# LED_Array.net
KiCad netlist of a schematic drawn in Altium Designer
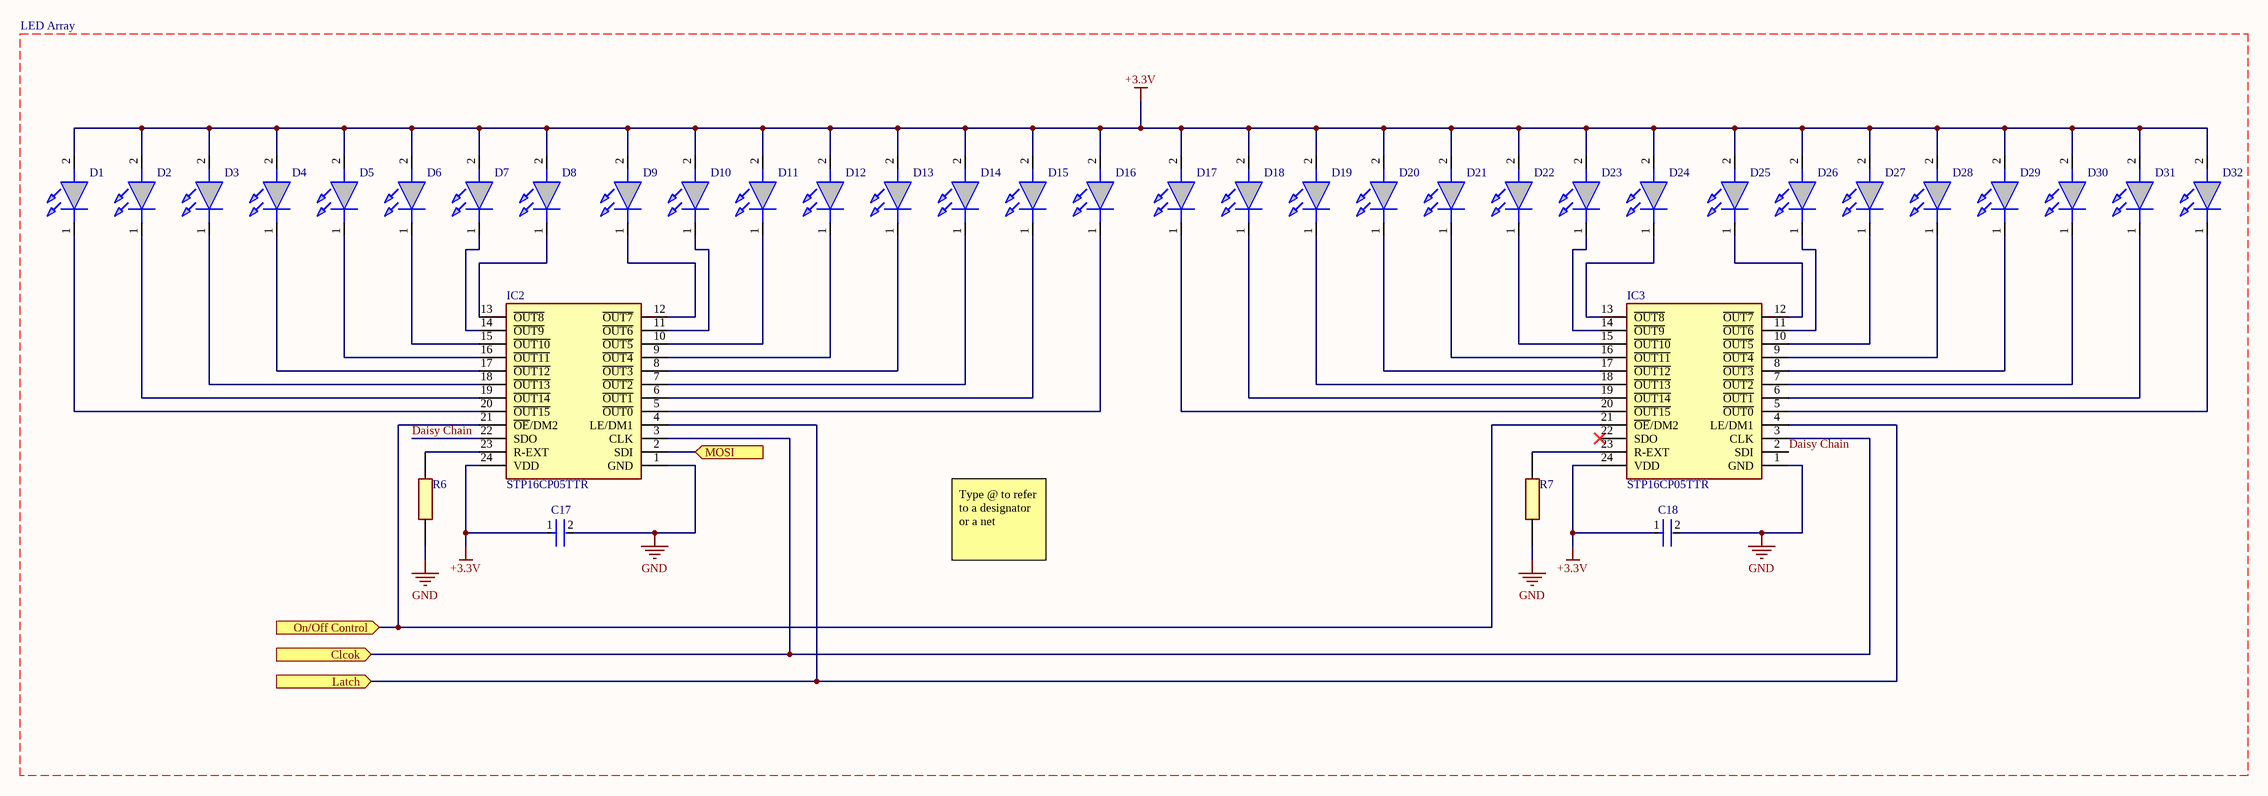
[diagram p0: LED_Array.SchDoc]

(export (version "E")
  (design (tool "Eeschema 10.0.6"))
  (components
    (comp (ref "C17")
      (value "CL31B104KBP5PNF")
      (footprint "FP-CL31-IPC_C")
      (description "Cap Ceramic 100nF 50V X7R ±10% SMD 1206 +125°C Embossed T/R")
      (fields (field (name "TOLERANCE") "10%"))
      (libsource (lib "Altium Content Vault") (part "b4654b650e69147ec39a6b967a45e02"))
    )
    (comp (ref "C18")
      (value "CL31B104KBP5PNF")
      (footprint "FP-CL31-IPC_C")
      (description "Cap Ceramic 100nF 50V X7R ±10% SMD 1206 +125°C Embossed T/R")
      (fields (field (name "TOLERANCE") "10%"))
      (libsource (lib "Altium Content Vault") (part "b4654b650e69147ec39a6b967a45e02"))
    )
    (comp (ref "D1")
      (value "LR_T64F-BBDB-1-1")
      (footprint "LEDM3528X380N")
      (description "Standard LEDs - SMD Red")
      (fields
        (field (name "MOUSER PART NUMBER") "720-LRT64FBBDB11")
        (field (name "MANUFACTURER_PART_NUMBER") "LR T64F-BBDB-1-1")
      )
      (libsource (lib "LR_T64F-BBDB-1-1") (part "LR_T64F-BBDB-1-1"))
    )
    (comp (ref "D2")
      (value "LR_T64F-BBDB-1-1")
      (footprint "LEDM3528X380N")
      (description "Standard LEDs - SMD Red")
      (fields
        (field (name "MOUSER PART NUMBER") "720-LRT64FBBDB11")
        (field (name "MANUFACTURER_PART_NUMBER") "LR T64F-BBDB-1-1")
      )
      (libsource (lib "LR_T64F-BBDB-1-1") (part "LR_T64F-BBDB-1-1"))
    )
    (comp (ref "D3")
      (value "LR_T64F-BBDB-1-1")
      (footprint "LEDM3528X380N")
      (description "Standard LEDs - SMD Red")
      (fields
        (field (name "MOUSER PART NUMBER") "720-LRT64FBBDB11")
        (field (name "MANUFACTURER_PART_NUMBER") "LR T64F-BBDB-1-1")
      )
      (libsource (lib "LR_T64F-BBDB-1-1") (part "LR_T64F-BBDB-1-1"))
    )
    (comp (ref "D4")
      (value "LR_T64F-BBDB-1-1")
      (footprint "LEDM3528X380N")
      (description "Standard LEDs - SMD Red")
      (fields
        (field (name "MOUSER PART NUMBER") "720-LRT64FBBDB11")
        (field (name "MANUFACTURER_PART_NUMBER") "LR T64F-BBDB-1-1")
      )
      (libsource (lib "LR_T64F-BBDB-1-1") (part "LR_T64F-BBDB-1-1"))
    )
    (comp (ref "D5")
      (value "LR_T64F-BBDB-1-1")
      (footprint "LEDM3528X380N")
      (description "Standard LEDs - SMD Red")
      (fields
        (field (name "MOUSER PART NUMBER") "720-LRT64FBBDB11")
        (field (name "MANUFACTURER_PART_NUMBER") "LR T64F-BBDB-1-1")
      )
      (libsource (lib "LR_T64F-BBDB-1-1") (part "LR_T64F-BBDB-1-1"))
    )
    (comp (ref "D6")
      (value "LR_T64F-BBDB-1-1")
      (footprint "LEDM3528X380N")
      (description "Standard LEDs - SMD Red")
      (fields
        (field (name "MOUSER PART NUMBER") "720-LRT64FBBDB11")
        (field (name "MANUFACTURER_PART_NUMBER") "LR T64F-BBDB-1-1")
      )
      (libsource (lib "LR_T64F-BBDB-1-1") (part "LR_T64F-BBDB-1-1"))
    )
    (comp (ref "D7")
      (value "LR_T64F-BBDB-1-1")
      (footprint "LEDM3528X380N")
      (description "Standard LEDs - SMD Red")
      (fields
        (field (name "MOUSER PART NUMBER") "720-LRT64FBBDB11")
        (field (name "MANUFACTURER_PART_NUMBER") "LR T64F-BBDB-1-1")
      )
      (libsource (lib "LR_T64F-BBDB-1-1") (part "LR_T64F-BBDB-1-1"))
    )
    (comp (ref "D8")
      (value "LR_T64F-BBDB-1-1")
      (footprint "LEDM3528X380N")
      (description "Standard LEDs - SMD Red")
      (fields
        (field (name "MOUSER PART NUMBER") "720-LRT64FBBDB11")
        (field (name "MANUFACTURER_PART_NUMBER") "LR T64F-BBDB-1-1")
      )
      (libsource (lib "LR_T64F-BBDB-1-1") (part "LR_T64F-BBDB-1-1"))
    )
    (comp (ref "D9")
      (value "LR_T64F-BBDB-1-1")
      (footprint "LEDM3528X380N")
      (description "Standard LEDs - SMD Red")
      (fields
        (field (name "MOUSER PART NUMBER") "720-LRT64FBBDB11")
        (field (name "MANUFACTURER_PART_NUMBER") "LR T64F-BBDB-1-1")
      )
      (libsource (lib "LR_T64F-BBDB-1-1") (part "LR_T64F-BBDB-1-1"))
    )
    (comp (ref "D10")
      (value "LR_T64F-BBDB-1-1")
      (footprint "LEDM3528X380N")
      (description "Standard LEDs - SMD Red")
      (fields
        (field (name "MOUSER PART NUMBER") "720-LRT64FBBDB11")
        (field (name "MANUFACTURER_PART_NUMBER") "LR T64F-BBDB-1-1")
      )
      (libsource (lib "LR_T64F-BBDB-1-1") (part "LR_T64F-BBDB-1-1"))
    )
    (comp (ref "D11")
      (value "LR_T64F-BBDB-1-1")
      (footprint "LEDM3528X380N")
      (description "Standard LEDs - SMD Red")
      (fields
        (field (name "MOUSER PART NUMBER") "720-LRT64FBBDB11")
        (field (name "MANUFACTURER_PART_NUMBER") "LR T64F-BBDB-1-1")
      )
      (libsource (lib "LR_T64F-BBDB-1-1") (part "LR_T64F-BBDB-1-1"))
    )
    (comp (ref "D12")
      (value "LR_T64F-BBDB-1-1")
      (footprint "LEDM3528X380N")
      (description "Standard LEDs - SMD Red")
      (fields
        (field (name "MOUSER PART NUMBER") "720-LRT64FBBDB11")
        (field (name "MANUFACTURER_PART_NUMBER") "LR T64F-BBDB-1-1")
      )
      (libsource (lib "LR_T64F-BBDB-1-1") (part "LR_T64F-BBDB-1-1"))
    )
    (comp (ref "D13")
      (value "LR_T64F-BBDB-1-1")
      (footprint "LEDM3528X380N")
      (description "Standard LEDs - SMD Red")
      (fields
        (field (name "MOUSER PART NUMBER") "720-LRT64FBBDB11")
        (field (name "MANUFACTURER_PART_NUMBER") "LR T64F-BBDB-1-1")
      )
      (libsource (lib "LR_T64F-BBDB-1-1") (part "LR_T64F-BBDB-1-1"))
    )
    (comp (ref "D14")
      (value "LR_T64F-BBDB-1-1")
      (footprint "LEDM3528X380N")
      (description "Standard LEDs - SMD Red")
      (fields
        (field (name "MOUSER PART NUMBER") "720-LRT64FBBDB11")
        (field (name "MANUFACTURER_PART_NUMBER") "LR T64F-BBDB-1-1")
      )
      (libsource (lib "LR_T64F-BBDB-1-1") (part "LR_T64F-BBDB-1-1"))
    )
    (comp (ref "D15")
      (value "LR_T64F-BBDB-1-1")
      (footprint "LEDM3528X380N")
      (description "Standard LEDs - SMD Red")
      (fields
        (field (name "MOUSER PART NUMBER") "720-LRT64FBBDB11")
        (field (name "MANUFACTURER_PART_NUMBER") "LR T64F-BBDB-1-1")
      )
      (libsource (lib "LR_T64F-BBDB-1-1") (part "LR_T64F-BBDB-1-1"))
    )
    (comp (ref "D16")
      (value "LR_T64F-BBDB-1-1")
      (footprint "LEDM3528X380N")
      (description "Standard LEDs - SMD Red")
      (fields
        (field (name "MOUSER PART NUMBER") "720-LRT64FBBDB11")
        (field (name "MANUFACTURER_PART_NUMBER") "LR T64F-BBDB-1-1")
      )
      (libsource (lib "LR_T64F-BBDB-1-1") (part "LR_T64F-BBDB-1-1"))
    )
    (comp (ref "D17")
      (value "LR_T64F-BBDB-1-1")
      (footprint "LEDM3528X380N")
      (description "Standard LEDs - SMD Red")
      (fields
        (field (name "MOUSER PART NUMBER") "720-LRT64FBBDB11")
        (field (name "MANUFACTURER_PART_NUMBER") "LR T64F-BBDB-1-1")
      )
      (libsource (lib "LR_T64F-BBDB-1-1") (part "LR_T64F-BBDB-1-1"))
    )
    (comp (ref "D18")
      (value "LR_T64F-BBDB-1-1")
      (footprint "LEDM3528X380N")
      (description "Standard LEDs - SMD Red")
      (fields
        (field (name "MOUSER PART NUMBER") "720-LRT64FBBDB11")
        (field (name "MANUFACTURER_PART_NUMBER") "LR T64F-BBDB-1-1")
      )
      (libsource (lib "LR_T64F-BBDB-1-1") (part "LR_T64F-BBDB-1-1"))
    )
    (comp (ref "D19")
      (value "LR_T64F-BBDB-1-1")
      (footprint "LEDM3528X380N")
      (description "Standard LEDs - SMD Red")
      (fields
        (field (name "MOUSER PART NUMBER") "720-LRT64FBBDB11")
        (field (name "MANUFACTURER_PART_NUMBER") "LR T64F-BBDB-1-1")
      )
      (libsource (lib "LR_T64F-BBDB-1-1") (part "LR_T64F-BBDB-1-1"))
    )
    (comp (ref "D20")
      (value "LR_T64F-BBDB-1-1")
      (footprint "LEDM3528X380N")
      (description "Standard LEDs - SMD Red")
      (fields
        (field (name "MOUSER PART NUMBER") "720-LRT64FBBDB11")
        (field (name "MANUFACTURER_PART_NUMBER") "LR T64F-BBDB-1-1")
      )
      (libsource (lib "LR_T64F-BBDB-1-1") (part "LR_T64F-BBDB-1-1"))
    )
    (comp (ref "D21")
      (value "LR_T64F-BBDB-1-1")
      (footprint "LEDM3528X380N")
      (description "Standard LEDs - SMD Red")
      (fields
        (field (name "MOUSER PART NUMBER") "720-LRT64FBBDB11")
        (field (name "MANUFACTURER_PART_NUMBER") "LR T64F-BBDB-1-1")
      )
      (libsource (lib "LR_T64F-BBDB-1-1") (part "LR_T64F-BBDB-1-1"))
    )
    (comp (ref "D22")
      (value "LR_T64F-BBDB-1-1")
      (footprint "LEDM3528X380N")
      (description "Standard LEDs - SMD Red")
      (fields
        (field (name "MOUSER PART NUMBER") "720-LRT64FBBDB11")
        (field (name "MANUFACTURER_PART_NUMBER") "LR T64F-BBDB-1-1")
      )
      (libsource (lib "LR_T64F-BBDB-1-1") (part "LR_T64F-BBDB-1-1"))
    )
    (comp (ref "D23")
      (value "LR_T64F-BBDB-1-1")
      (footprint "LEDM3528X380N")
      (description "Standard LEDs - SMD Red")
      (fields
        (field (name "MOUSER PART NUMBER") "720-LRT64FBBDB11")
        (field (name "MANUFACTURER_PART_NUMBER") "LR T64F-BBDB-1-1")
      )
      (libsource (lib "LR_T64F-BBDB-1-1") (part "LR_T64F-BBDB-1-1"))
    )
    (comp (ref "D24")
      (value "LR_T64F-BBDB-1-1")
      (footprint "LEDM3528X380N")
      (description "Standard LEDs - SMD Red")
      (fields
        (field (name "MOUSER PART NUMBER") "720-LRT64FBBDB11")
        (field (name "MANUFACTURER_PART_NUMBER") "LR T64F-BBDB-1-1")
      )
      (libsource (lib "LR_T64F-BBDB-1-1") (part "LR_T64F-BBDB-1-1"))
    )
    (comp (ref "D25")
      (value "LR_T64F-BBDB-1-1")
      (footprint "LEDM3528X380N")
      (description "Standard LEDs - SMD Red")
      (fields
        (field (name "MOUSER PART NUMBER") "720-LRT64FBBDB11")
        (field (name "MANUFACTURER_PART_NUMBER") "LR T64F-BBDB-1-1")
      )
      (libsource (lib "LR_T64F-BBDB-1-1") (part "LR_T64F-BBDB-1-1"))
    )
    (comp (ref "D26")
      (value "LR_T64F-BBDB-1-1")
      (footprint "LEDM3528X380N")
      (description "Standard LEDs - SMD Red")
      (fields
        (field (name "MOUSER PART NUMBER") "720-LRT64FBBDB11")
        (field (name "MANUFACTURER_PART_NUMBER") "LR T64F-BBDB-1-1")
      )
      (libsource (lib "LR_T64F-BBDB-1-1") (part "LR_T64F-BBDB-1-1"))
    )
    (comp (ref "D27")
      (value "LR_T64F-BBDB-1-1")
      (footprint "LEDM3528X380N")
      (description "Standard LEDs - SMD Red")
      (fields
        (field (name "MOUSER PART NUMBER") "720-LRT64FBBDB11")
        (field (name "MANUFACTURER_PART_NUMBER") "LR T64F-BBDB-1-1")
      )
      (libsource (lib "LR_T64F-BBDB-1-1") (part "LR_T64F-BBDB-1-1"))
    )
    (comp (ref "D28")
      (value "LR_T64F-BBDB-1-1")
      (footprint "LEDM3528X380N")
      (description "Standard LEDs - SMD Red")
      (fields
        (field (name "MOUSER PART NUMBER") "720-LRT64FBBDB11")
        (field (name "MANUFACTURER_PART_NUMBER") "LR T64F-BBDB-1-1")
      )
      (libsource (lib "LR_T64F-BBDB-1-1") (part "LR_T64F-BBDB-1-1"))
    )
    (comp (ref "D29")
      (value "LR_T64F-BBDB-1-1")
      (footprint "LEDM3528X380N")
      (description "Standard LEDs - SMD Red")
      (fields
        (field (name "MOUSER PART NUMBER") "720-LRT64FBBDB11")
        (field (name "MANUFACTURER_PART_NUMBER") "LR T64F-BBDB-1-1")
      )
      (libsource (lib "LR_T64F-BBDB-1-1") (part "LR_T64F-BBDB-1-1"))
    )
    (comp (ref "D30")
      (value "LR_T64F-BBDB-1-1")
      (footprint "LEDM3528X380N")
      (description "Standard LEDs - SMD Red")
      (fields
        (field (name "MOUSER PART NUMBER") "720-LRT64FBBDB11")
        (field (name "MANUFACTURER_PART_NUMBER") "LR T64F-BBDB-1-1")
      )
      (libsource (lib "LR_T64F-BBDB-1-1") (part "LR_T64F-BBDB-1-1"))
    )
    (comp (ref "D31")
      (value "LR_T64F-BBDB-1-1")
      (footprint "LEDM3528X380N")
      (description "Standard LEDs - SMD Red")
      (fields
        (field (name "MOUSER PART NUMBER") "720-LRT64FBBDB11")
        (field (name "MANUFACTURER_PART_NUMBER") "LR T64F-BBDB-1-1")
      )
      (libsource (lib "LR_T64F-BBDB-1-1") (part "LR_T64F-BBDB-1-1"))
    )
    (comp (ref "D32")
      (value "LR_T64F-BBDB-1-1")
      (footprint "LEDM3528X380N")
      (description "Standard LEDs - SMD Red")
      (fields
        (field (name "MOUSER PART NUMBER") "720-LRT64FBBDB11")
        (field (name "MANUFACTURER_PART_NUMBER") "LR T64F-BBDB-1-1")
      )
      (libsource (lib "LR_T64F-BBDB-1-1") (part "LR_T64F-BBDB-1-1"))
    )
    (comp (ref "IC2")
      (value "STP16CP05TTR")
      (footprint "SOP65P638X110-24N")
      (description "STMICROELECTRONICS - STP16CP05TTR - IC LED SINK DRIVER, 16-BIT, LO V")
      (fields (field (name "MOUSER PART NUMBER") "511-STP16CP05TTR"))
      (libsource (lib "STP16CP05TTR") (part "STP16CP05TTR"))
    )
    (comp (ref "IC3")
      (value "STP16CP05TTR")
      (footprint "SOP65P638X110-24N")
      (description "STMICROELECTRONICS - STP16CP05TTR - IC LED SINK DRIVER, 16-BIT, LO V")
      (fields (field (name "MOUSER PART NUMBER") "511-STP16CP05TTR"))
      (libsource (lib "STP16CP05TTR") (part "STP16CP05TTR"))
    )
    (comp (ref "R6")
      (value "ERA-8APB122V")
      (footprint "RESC3216X70N")
      (description "Thin Film Resistors - SMD 1206 Thin film chip resistor")
      (fields (field (name "MOUSER PART NUMBER") "667-ERA-8APB122V"))
      (libsource (lib "ERA-8APB122V") (part "ERA-8APB122V"))
    )
    (comp (ref "R7")
      (value "ERA-8APB122V")
      (footprint "RESC3216X70N")
      (description "Thin Film Resistors - SMD 1206 Thin film chip resistor")
      (fields (field (name "MOUSER PART NUMBER") "667-ERA-8APB122V"))
      (libsource (lib "ERA-8APB122V") (part "ERA-8APB122V"))
    )
  )
  (nets
    (net (code "1") (name "+3.3V") (class "Default")
      (node (ref "C17") (pin "1") (pinfunction "1_1") (pintype "passive"))
      (node (ref "C18") (pin "1") (pinfunction "1_1") (pintype "passive"))
      (node (ref "D1") (pin "2") (pinfunction "A_2") (pintype "passive"))
      (node (ref "D10") (pin "2") (pinfunction "A_2") (pintype "passive"))
      (node (ref "D11") (pin "2") (pinfunction "A_2") (pintype "passive"))
      (node (ref "D12") (pin "2") (pinfunction "A_2") (pintype "passive"))
      (node (ref "D13") (pin "2") (pinfunction "A_2") (pintype "passive"))
      (node (ref "D14") (pin "2") (pinfunction "A_2") (pintype "passive"))
      (node (ref "D15") (pin "2") (pinfunction "A_2") (pintype "passive"))
      (node (ref "D16") (pin "2") (pinfunction "A_2") (pintype "passive"))
      (node (ref "D17") (pin "2") (pinfunction "A_2") (pintype "passive"))
      (node (ref "D18") (pin "2") (pinfunction "A_2") (pintype "passive"))
      (node (ref "D19") (pin "2") (pinfunction "A_2") (pintype "passive"))
      (node (ref "D2") (pin "2") (pinfunction "A_2") (pintype "passive"))
      (node (ref "D20") (pin "2") (pinfunction "A_2") (pintype "passive"))
      (node (ref "D21") (pin "2") (pinfunction "A_2") (pintype "passive"))
      (node (ref "D22") (pin "2") (pinfunction "A_2") (pintype "passive"))
      (node (ref "D23") (pin "2") (pinfunction "A_2") (pintype "passive"))
      (node (ref "D24") (pin "2") (pinfunction "A_2") (pintype "passive"))
      (node (ref "D25") (pin "2") (pinfunction "A_2") (pintype "passive"))
      (node (ref "D26") (pin "2") (pinfunction "A_2") (pintype "passive"))
      (node (ref "D27") (pin "2") (pinfunction "A_2") (pintype "passive"))
      (node (ref "D28") (pin "2") (pinfunction "A_2") (pintype "passive"))
      (node (ref "D29") (pin "2") (pinfunction "A_2") (pintype "passive"))
      (node (ref "D3") (pin "2") (pinfunction "A_2") (pintype "passive"))
      (node (ref "D30") (pin "2") (pinfunction "A_2") (pintype "passive"))
      (node (ref "D31") (pin "2") (pinfunction "A_2") (pintype "passive"))
      (node (ref "D32") (pin "2") (pinfunction "A_2") (pintype "passive"))
      (node (ref "D4") (pin "2") (pinfunction "A_2") (pintype "passive"))
      (node (ref "D5") (pin "2") (pinfunction "A_2") (pintype "passive"))
      (node (ref "D6") (pin "2") (pinfunction "A_2") (pintype "passive"))
      (node (ref "D7") (pin "2") (pinfunction "A_2") (pintype "passive"))
      (node (ref "D8") (pin "2") (pinfunction "A_2") (pintype "passive"))
      (node (ref "D9") (pin "2") (pinfunction "A_2") (pintype "passive"))
      (node (ref "IC2") (pin "24") (pinfunction "VDD_24") (pintype "passive"))
      (node (ref "IC3") (pin "24") (pinfunction "VDD_24") (pintype "passive"))
    )
    (net (code "2") (name "/Clcok") (class "Default")
      (node (ref "IC2") (pin "3") (pinfunction "CLK_3") (pintype "passive"))
      (node (ref "IC3") (pin "3") (pinfunction "CLK_3") (pintype "passive"))
    )
    (net (code "3") (name "/Daisy Chain") (class "Default")
      (node (ref "IC2") (pin "22") (pinfunction "SDO_22") (pintype "passive"))
      (node (ref "IC3") (pin "2") (pinfunction "SDI_2") (pintype "passive"))
    )
    (net (code "4") (name "/Latch") (class "Default")
      (node (ref "IC2") (pin "4") (pinfunction "LE/DM1_4") (pintype "passive"))
      (node (ref "IC3") (pin "4") (pinfunction "LE/DM1_4") (pintype "passive"))
    )
    (net (code "5") (name "/MOSI") (class "Default")
      (node (ref "IC2") (pin "2") (pinfunction "SDI_2") (pintype "passive"))
    )
    (net (code "6") (name "/On{slash}Off Control") (class "Default")
      (node (ref "IC2") (pin "21") (pinfunction "~{OE}/DM2_21") (pintype "passive"))
      (node (ref "IC3") (pin "21") (pinfunction "~{OE}/DM2_21") (pintype "passive"))
    )
    (net (code "7") (name "GND") (class "Default")
      (node (ref "C17") (pin "2") (pinfunction "2_2") (pintype "passive"))
      (node (ref "C18") (pin "2") (pinfunction "2_2") (pintype "passive"))
      (node (ref "IC2") (pin "1") (pinfunction "GND_1") (pintype "passive"))
      (node (ref "IC3") (pin "1") (pinfunction "GND_1") (pintype "passive"))
      (node (ref "R6") (pin "1") (pinfunction "1_1") (pintype "passive"))
      (node (ref "R7") (pin "1") (pinfunction "1_1") (pintype "passive"))
    )
    (net (code "8") (name "Net-(D1-K)") (class "Default")
      (node (ref "D1") (pin "1") (pinfunction "K_1") (pintype "passive"))
      (node (ref "IC2") (pin "20") (pinfunction "~{OUT15}_20") (pintype "passive"))
    )
    (net (code "9") (name "Net-(D2-K)") (class "Default")
      (node (ref "D2") (pin "1") (pinfunction "K_1") (pintype "passive"))
      (node (ref "IC2") (pin "19") (pinfunction "~{OUT14}_19") (pintype "passive"))
    )
    (net (code "10") (name "Net-(D3-K)") (class "Default")
      (node (ref "D3") (pin "1") (pinfunction "K_1") (pintype "passive"))
      (node (ref "IC2") (pin "18") (pinfunction "~{OUT13}_18") (pintype "passive"))
    )
    (net (code "11") (name "Net-(D4-K)") (class "Default")
      (node (ref "D4") (pin "1") (pinfunction "K_1") (pintype "passive"))
      (node (ref "IC2") (pin "17") (pinfunction "~{OUT12}_17") (pintype "passive"))
    )
    (net (code "12") (name "Net-(D5-K)") (class "Default")
      (node (ref "D5") (pin "1") (pinfunction "K_1") (pintype "passive"))
      (node (ref "IC2") (pin "16") (pinfunction "~{OUT11}_16") (pintype "passive"))
    )
    (net (code "13") (name "Net-(D6-K)") (class "Default")
      (node (ref "D6") (pin "1") (pinfunction "K_1") (pintype "passive"))
      (node (ref "IC2") (pin "15") (pinfunction "~{OUT10}_15") (pintype "passive"))
    )
    (net (code "14") (name "Net-(D7-K)") (class "Default")
      (node (ref "D7") (pin "1") (pinfunction "K_1") (pintype "passive"))
      (node (ref "IC2") (pin "14") (pinfunction "~{OUT9}_14") (pintype "passive"))
    )
    (net (code "15") (name "Net-(D8-K)") (class "Default")
      (node (ref "D8") (pin "1") (pinfunction "K_1") (pintype "passive"))
      (node (ref "IC2") (pin "13") (pinfunction "~{OUT8}_13") (pintype "passive"))
    )
    (net (code "16") (name "Net-(D9-K)") (class "Default")
      (node (ref "D9") (pin "1") (pinfunction "K_1") (pintype "passive"))
      (node (ref "IC2") (pin "12") (pinfunction "~{OUT7}_12") (pintype "passive"))
    )
    (net (code "17") (name "Net-(D10-K)") (class "Default")
      (node (ref "D10") (pin "1") (pinfunction "K_1") (pintype "passive"))
      (node (ref "IC2") (pin "11") (pinfunction "~{OUT6}_11") (pintype "passive"))
    )
    (net (code "18") (name "Net-(D11-K)") (class "Default")
      (node (ref "D11") (pin "1") (pinfunction "K_1") (pintype "passive"))
      (node (ref "IC2") (pin "10") (pinfunction "~{OUT5}_10") (pintype "passive"))
    )
    (net (code "19") (name "Net-(D12-K)") (class "Default")
      (node (ref "D12") (pin "1") (pinfunction "K_1") (pintype "passive"))
      (node (ref "IC2") (pin "9") (pinfunction "~{OUT4}_9") (pintype "passive"))
    )
    (net (code "20") (name "Net-(D13-K)") (class "Default")
      (node (ref "D13") (pin "1") (pinfunction "K_1") (pintype "passive"))
      (node (ref "IC2") (pin "8") (pinfunction "~{OUT3}_8") (pintype "passive"))
    )
    (net (code "21") (name "Net-(D14-K)") (class "Default")
      (node (ref "D14") (pin "1") (pinfunction "K_1") (pintype "passive"))
      (node (ref "IC2") (pin "7") (pinfunction "~{OUT2}_7") (pintype "passive"))
    )
    (net (code "22") (name "Net-(D15-K)") (class "Default")
      (node (ref "D15") (pin "1") (pinfunction "K_1") (pintype "passive"))
      (node (ref "IC2") (pin "6") (pinfunction "~{OUT1}_6") (pintype "passive"))
    )
    (net (code "23") (name "Net-(D16-K)") (class "Default")
      (node (ref "D16") (pin "1") (pinfunction "K_1") (pintype "passive"))
      (node (ref "IC2") (pin "5") (pinfunction "~{OUT0}_5") (pintype "passive"))
    )
    (net (code "24") (name "Net-(D17-K)") (class "Default")
      (node (ref "D17") (pin "1") (pinfunction "K_1") (pintype "passive"))
      (node (ref "IC3") (pin "20") (pinfunction "~{OUT15}_20") (pintype "passive"))
    )
    (net (code "25") (name "Net-(D18-K)") (class "Default")
      (node (ref "D18") (pin "1") (pinfunction "K_1") (pintype "passive"))
      (node (ref "IC3") (pin "19") (pinfunction "~{OUT14}_19") (pintype "passive"))
    )
    (net (code "26") (name "Net-(D19-K)") (class "Default")
      (node (ref "D19") (pin "1") (pinfunction "K_1") (pintype "passive"))
      (node (ref "IC3") (pin "18") (pinfunction "~{OUT13}_18") (pintype "passive"))
    )
    (net (code "27") (name "Net-(D20-K)") (class "Default")
      (node (ref "D20") (pin "1") (pinfunction "K_1") (pintype "passive"))
      (node (ref "IC3") (pin "17") (pinfunction "~{OUT12}_17") (pintype "passive"))
    )
    (net (code "28") (name "Net-(D21-K)") (class "Default")
      (node (ref "D21") (pin "1") (pinfunction "K_1") (pintype "passive"))
      (node (ref "IC3") (pin "16") (pinfunction "~{OUT11}_16") (pintype "passive"))
    )
    (net (code "29") (name "Net-(D22-K)") (class "Default")
      (node (ref "D22") (pin "1") (pinfunction "K_1") (pintype "passive"))
      (node (ref "IC3") (pin "15") (pinfunction "~{OUT10}_15") (pintype "passive"))
    )
    (net (code "30") (name "Net-(D23-K)") (class "Default")
      (node (ref "D23") (pin "1") (pinfunction "K_1") (pintype "passive"))
      (node (ref "IC3") (pin "14") (pinfunction "~{OUT9}_14") (pintype "passive"))
    )
    (net (code "31") (name "Net-(D24-K)") (class "Default")
      (node (ref "D24") (pin "1") (pinfunction "K_1") (pintype "passive"))
      (node (ref "IC3") (pin "13") (pinfunction "~{OUT8}_13") (pintype "passive"))
    )
    (net (code "32") (name "Net-(D25-K)") (class "Default")
      (node (ref "D25") (pin "1") (pinfunction "K_1") (pintype "passive"))
      (node (ref "IC3") (pin "12") (pinfunction "~{OUT7}_12") (pintype "passive"))
    )
    (net (code "33") (name "Net-(D26-K)") (class "Default")
      (node (ref "D26") (pin "1") (pinfunction "K_1") (pintype "passive"))
      (node (ref "IC3") (pin "11") (pinfunction "~{OUT6}_11") (pintype "passive"))
    )
    (net (code "34") (name "Net-(D27-K)") (class "Default")
      (node (ref "D27") (pin "1") (pinfunction "K_1") (pintype "passive"))
      (node (ref "IC3") (pin "10") (pinfunction "~{OUT5}_10") (pintype "passive"))
    )
    (net (code "35") (name "Net-(D28-K)") (class "Default")
      (node (ref "D28") (pin "1") (pinfunction "K_1") (pintype "passive"))
      (node (ref "IC3") (pin "9") (pinfunction "~{OUT4}_9") (pintype "passive"))
    )
    (net (code "36") (name "Net-(D29-K)") (class "Default")
      (node (ref "D29") (pin "1") (pinfunction "K_1") (pintype "passive"))
      (node (ref "IC3") (pin "8") (pinfunction "~{OUT3}_8") (pintype "passive"))
    )
    (net (code "37") (name "Net-(D30-K)") (class "Default")
      (node (ref "D30") (pin "1") (pinfunction "K_1") (pintype "passive"))
      (node (ref "IC3") (pin "7") (pinfunction "~{OUT2}_7") (pintype "passive"))
    )
    (net (code "38") (name "Net-(D31-K)") (class "Default")
      (node (ref "D31") (pin "1") (pinfunction "K_1") (pintype "passive"))
      (node (ref "IC3") (pin "6") (pinfunction "~{OUT1}_6") (pintype "passive"))
    )
    (net (code "39") (name "Net-(D32-K)") (class "Default")
      (node (ref "D32") (pin "1") (pinfunction "K_1") (pintype "passive"))
      (node (ref "IC3") (pin "5") (pinfunction "~{OUT0}_5") (pintype "passive"))
    )
    (net (code "40") (name "Net-(IC2-R-EXT)") (class "Default")
      (node (ref "IC2") (pin "23") (pinfunction "R-EXT_23") (pintype "passive"))
      (node (ref "R6") (pin "2") (pinfunction "2_2") (pintype "passive"))
    )
    (net (code "41") (name "Net-(IC3-R-EXT)") (class "Default")
      (node (ref "IC3") (pin "23") (pinfunction "R-EXT_23") (pintype "passive"))
      (node (ref "R7") (pin "2") (pinfunction "2_2") (pintype "passive"))
    )
    (net (code "42") (name "unconnected-(IC3-SDO-Pad22)") (class "Default")
      (node (ref "IC3") (pin "22") (pinfunction "SDO_22") (pintype "passive+no_connect"))
    )
  )
)
